# RADG-Connector-S05-V00.net
KiCad netlist of a schematic drawn in Altium Designer
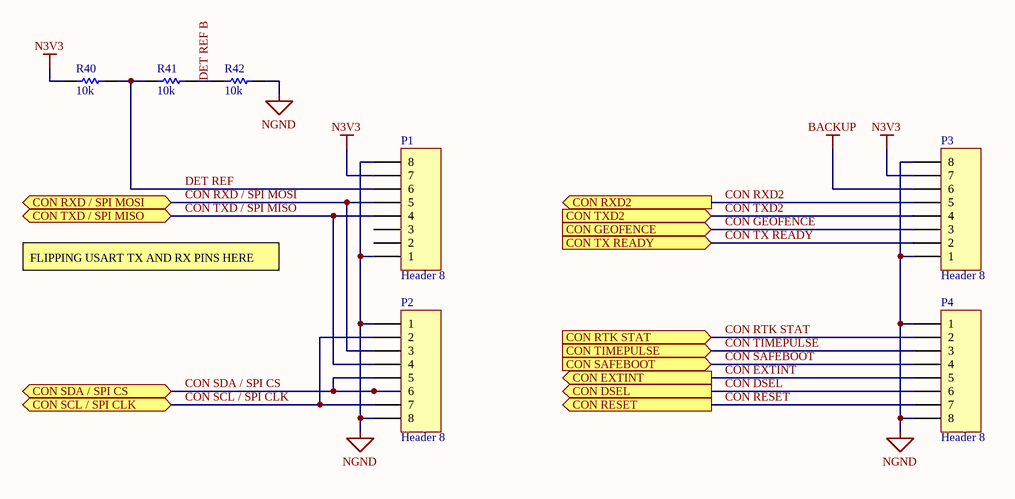
[diagram p0: RADG-Connector-S05-V00.SchDoc]

(export (version "E")
  (design (tool "Eeschema 10.0.6"))
  (components
    (comp (ref "P1")
      (value "Header 8")
      (footprint "HDR1X8")
      (description "Header, 8-Pin")
      (fields (field (name "PUBLISHER") "Altium Limited"))
      (libsource (lib "") (part "Header 8_1"))
    )
    (comp (ref "P2")
      (value "Header 8")
      (footprint "HDR1X8")
      (description "Header, 8-Pin")
      (fields (field (name "PUBLISHER") "Altium Limited"))
      (libsource (lib "Miscellaneous Connectors") (part "Header 8"))
    )
    (comp (ref "P3")
      (value "Header 8")
      (footprint "HDR1X8")
      (description "Header, 8-Pin")
      (fields (field (name "PUBLISHER") "Altium Limited"))
      (libsource (lib "") (part "Header 8_1"))
    )
    (comp (ref "P4")
      (value "Header 8")
      (footprint "HDR1X8")
      (description "Header, 8-Pin")
      (fields (field (name "PUBLISHER") "Altium Limited"))
      (libsource (lib "Miscellaneous Connectors") (part "Header 8"))
    )
    (comp (ref "R40")
      (value "10k")
      (footprint "Res_ThinFilm_0603")
      (description "Resistor, SMD, 10k, 0.1W, 5%, 0603")
      (libsource (lib "StandardResistors") (part "10k 5% 0603"))
    )
    (comp (ref "R41")
      (value "10k")
      (footprint "Res_ThinFilm_0603")
      (description "Resistor, SMD, 10k, 0.1W, 5%, 0603")
      (libsource (lib "StandardResistors") (part "10k 5% 0603"))
    )
    (comp (ref "R42")
      (value "10k")
      (footprint "Res_ThinFilm_0603")
      (description "Resistor, SMD, 10k, 0.1W, 5%, 0603")
      (libsource (lib "StandardResistors") (part "10k 5% 0603"))
    )
  )
  (nets
    (net (code "1") (name "/CON DSEL") (class "Default")
      (node (ref "P4") (pin "6") (pinfunction "6_6") (pintype "passive"))
    )
    (net (code "2") (name "/CON EXTINT") (class "Default")
      (node (ref "P4") (pin "5") (pinfunction "5_5") (pintype "passive"))
    )
    (net (code "3") (name "/CON GEOFENCE") (class "Default")
      (node (ref "P3") (pin "3") (pinfunction "3_3") (pintype "passive"))
    )
    (net (code "4") (name "/CON RESET") (class "Default")
      (node (ref "P4") (pin "7") (pinfunction "7_7") (pintype "passive"))
    )
    (net (code "5") (name "/CON RTK STAT") (class "Default")
      (node (ref "P4") (pin "2") (pinfunction "2_2") (pintype "passive"))
    )
    (net (code "6") (name "/CON RXD {slash} SPI MOSI") (class "Default")
      (node (ref "P1") (pin "5") (pinfunction "5_5") (pintype "passive"))
      (node (ref "P2") (pin "3") (pinfunction "3_3") (pintype "passive"))
    )
    (net (code "7") (name "/CON RXD2") (class "Default")
      (node (ref "P3") (pin "5") (pinfunction "5_5") (pintype "passive"))
    )
    (net (code "8") (name "/CON SAFEBOOT") (class "Default")
      (node (ref "P4") (pin "4") (pinfunction "4_4") (pintype "passive"))
    )
    (net (code "9") (name "/CON SCL {slash} SPI CLK") (class "Default")
      (node (ref "P2") (pin "2") (pinfunction "2_2") (pintype "passive"))
      (node (ref "P2") (pin "7") (pinfunction "7_7") (pintype "passive"))
    )
    (net (code "10") (name "/CON SDA {slash} SPI CS") (class "Default")
      (node (ref "P2") (pin "5") (pinfunction "5_5") (pintype "passive"))
      (node (ref "P2") (pin "6") (pinfunction "6_6") (pintype "passive"))
    )
    (net (code "11") (name "/CON TIMEPULSE") (class "Default")
      (node (ref "P4") (pin "3") (pinfunction "3_3") (pintype "passive"))
    )
    (net (code "12") (name "/CON TX READY") (class "Default")
      (node (ref "P3") (pin "2") (pinfunction "2_2") (pintype "passive"))
    )
    (net (code "13") (name "/CON TXD {slash} SPI MISO") (class "Default")
      (node (ref "P1") (pin "4") (pinfunction "4_4") (pintype "passive"))
      (node (ref "P2") (pin "4") (pinfunction "4_4") (pintype "passive"))
    )
    (net (code "14") (name "/CON TXD2") (class "Default")
      (node (ref "P3") (pin "4") (pinfunction "4_4") (pintype "passive"))
    )
    (net (code "15") (name "/DET REF") (class "Default")
      (node (ref "P1") (pin "6") (pinfunction "6_6") (pintype "passive"))
      (node (ref "R40") (pin "2") (pinfunction "2_2") (pintype "passive"))
      (node (ref "R41") (pin "1") (pinfunction "1_1") (pintype "passive"))
    )
    (net (code "16") (name "/DET REF B") (class "Default")
      (node (ref "R41") (pin "2") (pinfunction "2_2") (pintype "passive"))
      (node (ref "R42") (pin "1") (pinfunction "1_1") (pintype "passive"))
    )
    (net (code "17") (name "BACKUP") (class "Default")
      (node (ref "P3") (pin "6") (pinfunction "6_6") (pintype "passive"))
    )
    (net (code "18") (name "N3V3") (class "Default")
      (node (ref "P1") (pin "7") (pinfunction "7_7") (pintype "passive"))
      (node (ref "P3") (pin "7") (pinfunction "7_7") (pintype "passive"))
      (node (ref "R40") (pin "1") (pinfunction "1_1") (pintype "passive"))
    )
    (net (code "19") (name "NGND") (class "Default")
      (node (ref "P1") (pin "1") (pinfunction "1_1") (pintype "passive"))
      (node (ref "P1") (pin "8") (pinfunction "8_8") (pintype "passive"))
      (node (ref "P2") (pin "1") (pinfunction "1_1") (pintype "passive"))
      (node (ref "P2") (pin "8") (pinfunction "8_8") (pintype "passive"))
      (node (ref "P3") (pin "1") (pinfunction "1_1") (pintype "passive"))
      (node (ref "P3") (pin "8") (pinfunction "8_8") (pintype "passive"))
      (node (ref "P4") (pin "1") (pinfunction "1_1") (pintype "passive"))
      (node (ref "P4") (pin "8") (pinfunction "8_8") (pintype "passive"))
      (node (ref "R42") (pin "2") (pinfunction "2_2") (pintype "passive"))
    )
    (net (code "20") (name "unconnected-(P1-Pad2)") (class "Default")
      (node (ref "P1") (pin "2") (pinfunction "2_2") (pintype "passive"))
    )
    (net (code "21") (name "unconnected-(P1-Pad3)") (class "Default")
      (node (ref "P1") (pin "3") (pinfunction "3_3") (pintype "passive"))
    )
  )
)
